# SHIELD.net
KiCad netlist of a schematic drawn in EAGLE
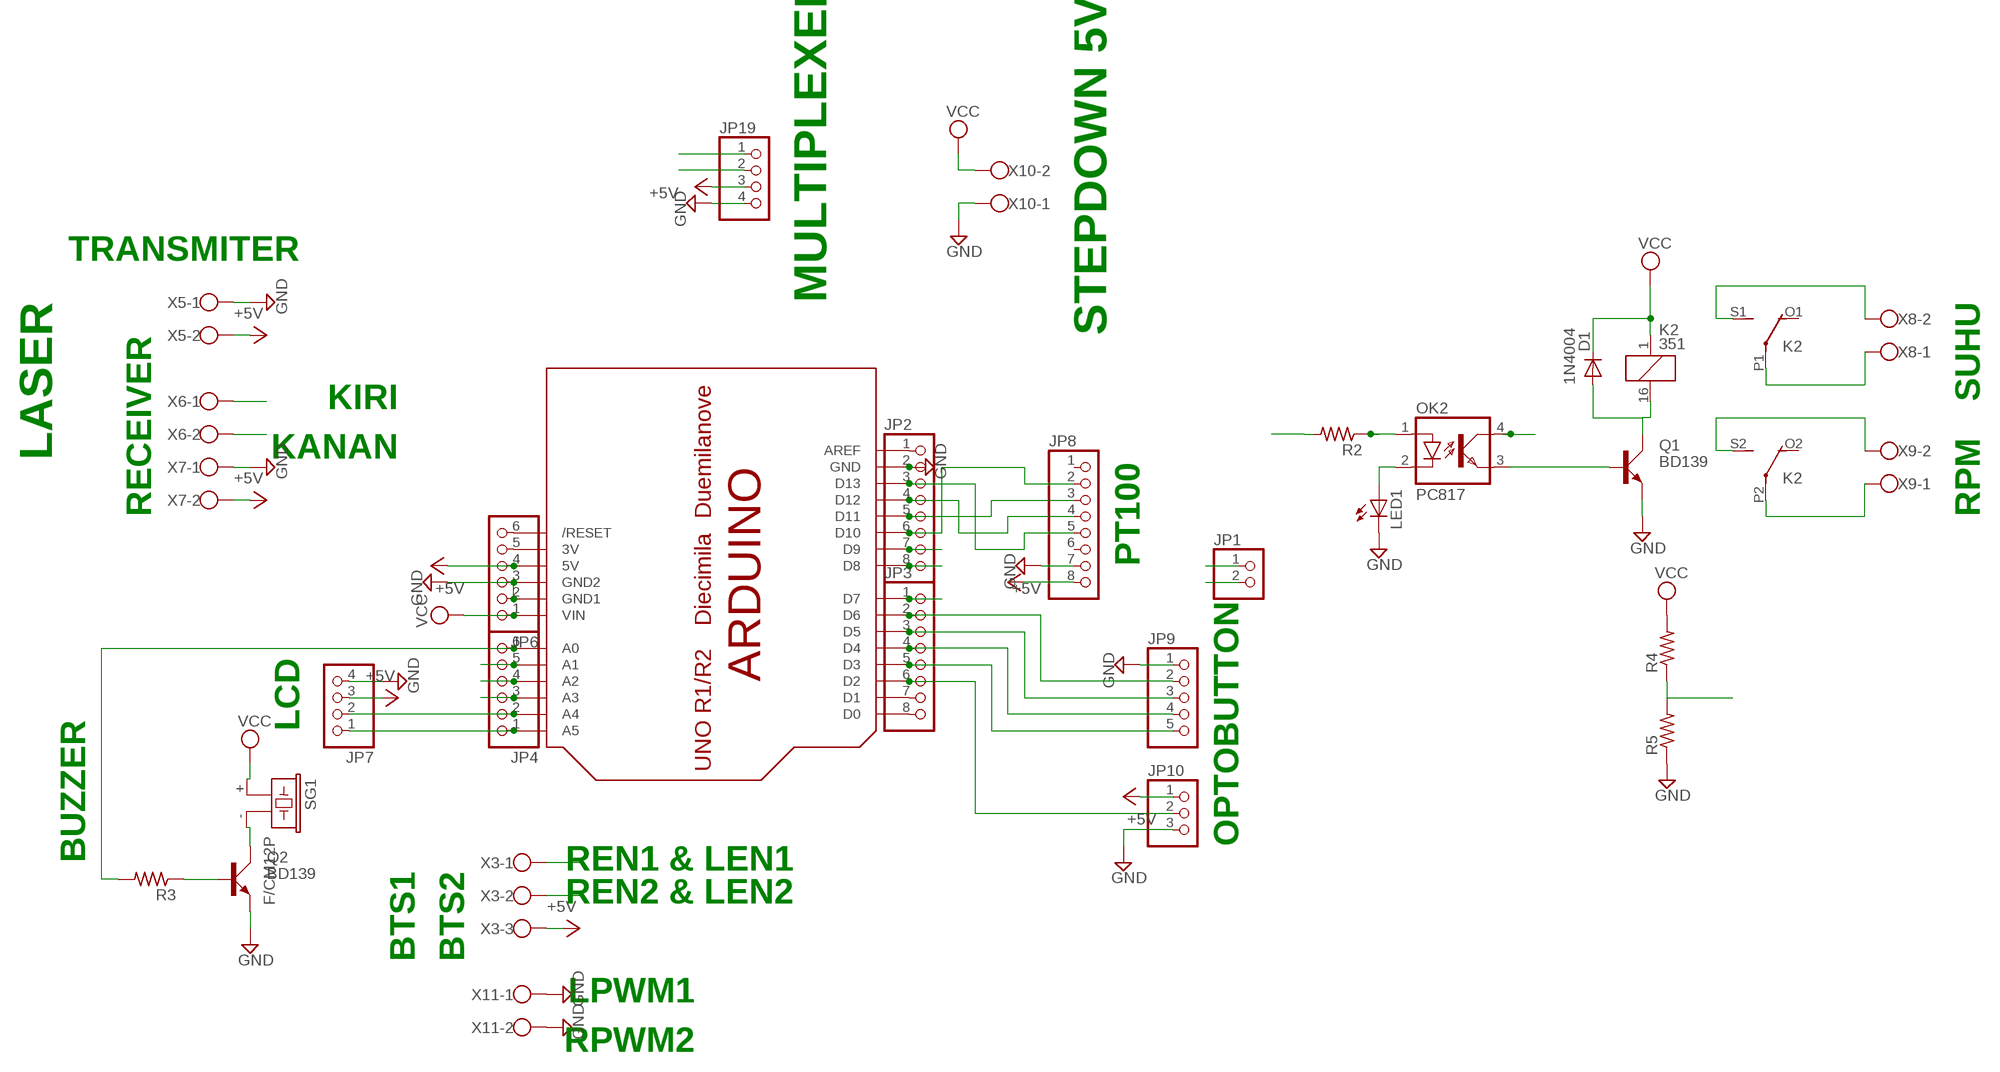
[diagram p0: schematic, sheet 1]

(export (version "E")
  (design (tool "Eeschema 10.0.6"))
  (components
    (comp (ref "D1")
      (value "1N4004")
      (footprint "eagle-import:DO41-10")
      (libsource (lib "eagle-import") (part "1N4004"))
    )
    (comp (ref "JP1")
      (value "PINHD-1X2")
      (footprint "eagle-import:1X02")
      (libsource (lib "eagle-import") (part "PINHD-1X2"))
    )
    (comp (ref "JP2")
      (value "PINHD-1X8")
      (footprint "eagle-import:1X08")
      (libsource (lib "eagle-import") (part "PINHD-1X8"))
    )
    (comp (ref "JP3")
      (value "PINHD-1X8")
      (footprint "eagle-import:1X08")
      (libsource (lib "eagle-import") (part "PINHD-1X8"))
    )
    (comp (ref "JP4")
      (value "PINHD-1X6")
      (footprint "eagle-import:1X06")
      (libsource (lib "eagle-import") (part "PINHD-1X6"))
    )
    (comp (ref "JP6")
      (value "PINHD-1X6")
      (footprint "eagle-import:1X06")
      (libsource (lib "eagle-import") (part "PINHD-1X6"))
    )
    (comp (ref "JP7")
      (value "PINHD-1X4")
      (footprint "eagle-import:1X04")
      (libsource (lib "eagle-import") (part "PINHD-1X4"))
    )
    (comp (ref "JP8")
      (value "PINHD-1X8")
      (footprint "eagle-import:1X08")
      (libsource (lib "eagle-import") (part "PINHD-1X8"))
    )
    (comp (ref "JP9")
      (value "PINHD-1X5")
      (footprint "eagle-import:1X05")
      (libsource (lib "eagle-import") (part "PINHD-1X5"))
    )
    (comp (ref "JP10")
      (value "PINHD-1X3")
      (footprint "eagle-import:1X03")
      (libsource (lib "eagle-import") (part "PINHD-1X3"))
    )
    (comp (ref "JP19")
      (value "PINHD-1X4")
      (footprint "eagle-import:1X04")
      (libsource (lib "eagle-import") (part "PINHD-1X4"))
    )
    (comp (ref "K2")
      (value "351")
      (footprint "eagle-import:351")
      (libsource (lib "eagle-import") (part "351"))
    )
    (comp (ref "LED1")
      (value "LED5MM")
      (footprint "eagle-import:LED5MM")
      (libsource (lib "eagle-import") (part "LED5MM"))
    )
    (comp (ref "OK2")
      (value "PC817")
      (footprint "eagle-import:DIL04")
      (fields (field (name "MPN") "PC817X4J000F"))
      (libsource (lib "eagle-import") (part "PC817"))
    )
    (comp (ref "Q1")
      (value "BD139")
      (footprint "eagle-import:TO126AV")
      (libsource (lib "eagle-import") (part "BD139"))
    )
    (comp (ref "Q2")
      (value "BD139")
      (footprint "eagle-import:TO126AV")
      (libsource (lib "eagle-import") (part "BD139"))
    )
    (comp (ref "R2")
      (value "R-US_0207/10")
      (footprint "eagle-import:0207_10")
      (libsource (lib "eagle-import") (part "R-US_0207/10"))
    )
    (comp (ref "R3")
      (value "R-US_0207/10")
      (footprint "eagle-import:0207_10")
      (libsource (lib "eagle-import") (part "R-US_0207/10"))
    )
    (comp (ref "R4")
      (value "R-US_0207/10")
      (footprint "eagle-import:0207_10")
      (libsource (lib "eagle-import") (part "R-US_0207/10"))
    )
    (comp (ref "R5")
      (value "R-US_0207/10")
      (footprint "eagle-import:0207_10")
      (libsource (lib "eagle-import") (part "R-US_0207/10"))
    )
    (comp (ref "SG1")
      (value "F/CM12P")
      (footprint "eagle-import:F_CM12P")
      (libsource (lib "eagle-import") (part "F/CM12P"))
    )
    (comp (ref "U$1")
      (value "ARDUINO-NOHOLE")
      (footprint "eagle-import:ARDUINO-NOHOLE")
      (libsource (lib "eagle-import") (part "ARDUINO-NOHOLE"))
    )
    (comp (ref "X3")
      (value "W237-103")
      (footprint "eagle-import:W237-103")
      (fields (field (name "MPN") "237-103"))
      (libsource (lib "eagle-import") (part "W237-103"))
    )
    (comp (ref "X5")
      (value "W237-102")
      (footprint "eagle-import:W237-102")
      (fields (field (name "MPN") "237-102"))
      (libsource (lib "eagle-import") (part "W237-102"))
    )
    (comp (ref "X6")
      (value "W237-102")
      (footprint "eagle-import:W237-102")
      (fields (field (name "MPN") "237-102"))
      (libsource (lib "eagle-import") (part "W237-102"))
    )
    (comp (ref "X7")
      (value "W237-102")
      (footprint "eagle-import:W237-102")
      (fields (field (name "MPN") "237-102"))
      (libsource (lib "eagle-import") (part "W237-102"))
    )
    (comp (ref "X8")
      (value "W237-102")
      (footprint "eagle-import:W237-102")
      (fields (field (name "MPN") "237-102"))
      (libsource (lib "eagle-import") (part "W237-102"))
    )
    (comp (ref "X9")
      (value "W237-102")
      (footprint "eagle-import:W237-102")
      (fields (field (name "MPN") "237-102"))
      (libsource (lib "eagle-import") (part "W237-102"))
    )
    (comp (ref "X10")
      (value "W237-102")
      (footprint "eagle-import:W237-102")
      (fields (field (name "MPN") "237-102"))
      (libsource (lib "eagle-import") (part "W237-102"))
    )
    (comp (ref "X11")
      (value "W237-102")
      (footprint "eagle-import:W237-102")
      (fields (field (name "MPN") "237-102"))
      (libsource (lib "eagle-import") (part "W237-102"))
    )
  )
  (nets
    (net (code "1") (name "+5V") (class "Default")
      (node (ref "JP10") (pin "1") (pinfunction "1_1") (pintype "passive"))
      (node (ref "JP19") (pin "3") (pinfunction "3_3") (pintype "passive"))
      (node (ref "JP6") (pin "4") (pinfunction "4_4") (pintype "passive"))
      (node (ref "JP7") (pin "3") (pinfunction "3_3") (pintype "passive"))
      (node (ref "JP8") (pin "8") (pinfunction "8_8") (pintype "passive"))
      (node (ref "U$1") (pin "5V") (pinfunction "5V_5V") (pintype "power_in"))
      (node (ref "X3") (pin "3") (pinfunction "KL_3") (pintype "passive"))
      (node (ref "X5") (pin "2") (pinfunction "KL_2") (pintype "passive"))
      (node (ref "X7") (pin "2") (pinfunction "KL_2") (pintype "passive"))
    )
    (net (code "2") (name "/N$1") (class "Default")
      (node (ref "JP1") (pin "1") (pinfunction "1_1") (pintype "passive"))
      (node (ref "JP1") (pin "2") (pinfunction "2_2") (pintype "passive"))
      (node (ref "JP2") (pin "7") (pinfunction "7_7") (pintype "passive"))
      (node (ref "U$1") (pin "D9") (pinfunction "D9_D9") (pintype "bidirectional"))
    )
    (net (code "3") (name "/N$9") (class "Default")
      (node (ref "JP19") (pin "2") (pinfunction "2_2") (pintype "passive"))
      (node (ref "JP4") (pin "2") (pinfunction "2_2") (pintype "passive"))
      (node (ref "JP7") (pin "2") (pinfunction "2_2") (pintype "passive"))
      (node (ref "U$1") (pin "A4") (pinfunction "A4_A4") (pintype "bidirectional"))
    )
    (net (code "4") (name "/N$10") (class "Default")
      (node (ref "JP19") (pin "1") (pinfunction "1_1") (pintype "passive"))
      (node (ref "JP4") (pin "1") (pinfunction "1_1") (pintype "passive"))
      (node (ref "JP7") (pin "1") (pinfunction "1_1") (pintype "passive"))
      (node (ref "U$1") (pin "A5") (pinfunction "A5_A5") (pintype "bidirectional"))
    )
    (net (code "5") (name "/N$26") (class "Default")
      (node (ref "JP4") (pin "4") (pinfunction "4_4") (pintype "passive"))
      (node (ref "U$1") (pin "A2") (pinfunction "A2_A2") (pintype "bidirectional"))
      (node (ref "X3") (pin "2") (pinfunction "KL_2") (pintype "passive"))
    )
    (net (code "6") (name "/N$27") (class "Default")
      (node (ref "JP3") (pin "1") (pinfunction "1_1") (pintype "passive"))
      (node (ref "U$1") (pin "D7") (pinfunction "D7_D7") (pintype "bidirectional"))
      (node (ref "X6") (pin "2") (pinfunction "KL_2") (pintype "passive"))
    )
    (net (code "7") (name "/N$28") (class "Default")
      (node (ref "JP4") (pin "5") (pinfunction "5_5") (pintype "passive"))
      (node (ref "U$1") (pin "A1") (pinfunction "A1_A1") (pintype "bidirectional"))
      (node (ref "X3") (pin "1") (pinfunction "KL_1") (pintype "passive"))
    )
    (net (code "8") (name "/N$29") (class "Default")
      (node (ref "JP2") (pin "8") (pinfunction "8_8") (pintype "passive"))
      (node (ref "U$1") (pin "D8") (pinfunction "D8_D8") (pintype "bidirectional"))
      (node (ref "X6") (pin "1") (pinfunction "KL_1") (pintype "passive"))
    )
    (net (code "9") (name "/N$32") (class "Default")
      (node (ref "JP4") (pin "3") (pinfunction "3_3") (pintype "passive"))
      (node (ref "R2") (pin "2") (pinfunction "2_2") (pintype "passive"))
      (node (ref "U$1") (pin "A3") (pinfunction "A3_A3") (pintype "bidirectional"))
    )
    (net (code "10") (name "/N$37") (class "Default")
      (node (ref "OK2") (pin "4") (pinfunction "COL_4") (pintype "passive"))
      (node (ref "R4") (pin "1") (pinfunction "1_1") (pintype "passive"))
      (node (ref "R5") (pin "2") (pinfunction "2_2") (pintype "passive"))
    )
    (net (code "11") (name "GND") (class "Default")
      (node (ref "JP10") (pin "3") (pinfunction "3_3") (pintype "passive"))
      (node (ref "JP19") (pin "4") (pinfunction "4_4") (pintype "passive"))
      (node (ref "JP2") (pin "2") (pinfunction "2_2") (pintype "passive"))
      (node (ref "JP6") (pin "2") (pinfunction "2_2") (pintype "passive"))
      (node (ref "JP6") (pin "3") (pinfunction "3_3") (pintype "passive"))
      (node (ref "JP7") (pin "4") (pinfunction "4_4") (pintype "passive"))
      (node (ref "JP8") (pin "7") (pinfunction "7_7") (pintype "passive"))
      (node (ref "JP9") (pin "1") (pinfunction "1_1") (pintype "passive"))
      (node (ref "LED1") (pin "K") (pinfunction "C_K") (pintype "passive"))
      (node (ref "Q1") (pin "E") (pinfunction "E_E") (pintype "passive"))
      (node (ref "Q2") (pin "E") (pinfunction "E_E") (pintype "passive"))
      (node (ref "R5") (pin "1") (pinfunction "1_1") (pintype "passive"))
      (node (ref "U$1") (pin "GND") (pinfunction "GND_GND") (pintype "power_in"))
      (node (ref "U$1") (pin "GND1") (pinfunction "GND1_GND1") (pintype "power_in"))
      (node (ref "U$1") (pin "GND2") (pinfunction "GND2_GND2") (pintype "power_in"))
      (node (ref "X10") (pin "1") (pinfunction "KL_1") (pintype "passive"))
      (node (ref "X11") (pin "1") (pinfunction "KL_1") (pintype "passive"))
      (node (ref "X11") (pin "2") (pinfunction "KL_2") (pintype "passive"))
      (node (ref "X5") (pin "1") (pinfunction "KL_1") (pintype "passive"))
      (node (ref "X7") (pin "1") (pinfunction "KL_1") (pintype "passive"))
    )
    (net (code "12") (name "Net-(JP2-Pad1)") (class "Default")
      (node (ref "JP2") (pin "1") (pinfunction "1_1") (pintype "passive"))
      (node (ref "U$1") (pin "AREF") (pinfunction "AREF_AREF") (pintype "bidirectional"))
    )
    (net (code "13") (name "Net-(JP2-Pad3)") (class "Default")
      (node (ref "JP2") (pin "3") (pinfunction "3_3") (pintype "passive"))
      (node (ref "JP8") (pin "5") (pinfunction "5_5") (pintype "passive"))
      (node (ref "U$1") (pin "D13") (pinfunction "D13_D13") (pintype "bidirectional"))
    )
    (net (code "14") (name "Net-(JP2-Pad4)") (class "Default")
      (node (ref "JP2") (pin "4") (pinfunction "4_4") (pintype "passive"))
      (node (ref "JP8") (pin "4") (pinfunction "4_4") (pintype "passive"))
      (node (ref "U$1") (pin "D12") (pinfunction "D12_D12") (pintype "bidirectional"))
    )
    (net (code "15") (name "Net-(JP2-Pad5)") (class "Default")
      (node (ref "JP2") (pin "5") (pinfunction "5_5") (pintype "passive"))
      (node (ref "JP8") (pin "3") (pinfunction "3_3") (pintype "passive"))
      (node (ref "U$1") (pin "D11") (pinfunction "D11_D11") (pintype "bidirectional"))
    )
    (net (code "16") (name "Net-(JP2-Pad6)") (class "Default")
      (node (ref "JP2") (pin "6") (pinfunction "6_6") (pintype "passive"))
      (node (ref "JP8") (pin "2") (pinfunction "2_2") (pintype "passive"))
      (node (ref "U$1") (pin "D10") (pinfunction "D10_D10") (pintype "bidirectional"))
    )
    (net (code "17") (name "Net-(JP3-Pad2)") (class "Default")
      (node (ref "JP3") (pin "2") (pinfunction "2_2") (pintype "passive"))
      (node (ref "JP9") (pin "2") (pinfunction "2_2") (pintype "passive"))
      (node (ref "U$1") (pin "D6") (pinfunction "D6_D6") (pintype "bidirectional"))
    )
    (net (code "18") (name "Net-(JP3-Pad3)") (class "Default")
      (node (ref "JP3") (pin "3") (pinfunction "3_3") (pintype "passive"))
      (node (ref "JP9") (pin "3") (pinfunction "3_3") (pintype "passive"))
      (node (ref "U$1") (pin "D5") (pinfunction "D5_D5") (pintype "bidirectional"))
    )
    (net (code "19") (name "Net-(JP3-Pad4)") (class "Default")
      (node (ref "JP3") (pin "4") (pinfunction "4_4") (pintype "passive"))
      (node (ref "JP9") (pin "4") (pinfunction "4_4") (pintype "passive"))
      (node (ref "U$1") (pin "D4") (pinfunction "D4_D4") (pintype "bidirectional"))
    )
    (net (code "20") (name "Net-(JP3-Pad5)") (class "Default")
      (node (ref "JP3") (pin "5") (pinfunction "5_5") (pintype "passive"))
      (node (ref "JP9") (pin "5") (pinfunction "5_5") (pintype "passive"))
      (node (ref "U$1") (pin "D3") (pinfunction "D3_D3") (pintype "bidirectional"))
    )
    (net (code "21") (name "Net-(JP3-Pad7)") (class "Default")
      (node (ref "JP3") (pin "7") (pinfunction "7_7") (pintype "passive"))
      (node (ref "U$1") (pin "D1") (pinfunction "D1_D1") (pintype "bidirectional"))
    )
    (net (code "22") (name "Net-(JP3-Pad8)") (class "Default")
      (node (ref "JP3") (pin "8") (pinfunction "8_8") (pintype "passive"))
      (node (ref "U$1") (pin "D0") (pinfunction "D0_D0") (pintype "bidirectional"))
    )
    (net (code "23") (name "Net-(JP4-Pad6)") (class "Default")
      (node (ref "JP4") (pin "6") (pinfunction "6_6") (pintype "passive"))
      (node (ref "R3") (pin "2") (pinfunction "2_2") (pintype "passive"))
      (node (ref "U$1") (pin "A0") (pinfunction "A0_A0") (pintype "bidirectional"))
    )
    (net (code "24") (name "Net-(JP6-Pad5)") (class "Default")
      (node (ref "JP6") (pin "5") (pinfunction "5_5") (pintype "passive"))
      (node (ref "U$1") (pin "3V") (pinfunction "3V_3V") (pintype "power_in"))
    )
    (net (code "25") (name "Net-(JP10-Pad2)") (class "Default")
      (node (ref "JP10") (pin "2") (pinfunction "2_2") (pintype "passive"))
      (node (ref "JP3") (pin "6") (pinfunction "6_6") (pintype "passive"))
      (node (ref "U$1") (pin "D2") (pinfunction "D2_D2") (pintype "bidirectional"))
    )
    (net (code "26") (name "Net-(K2A-2)") (class "Default")
      (node (ref "D1") (pin "A") (pinfunction "A_A") (pintype "passive"))
      (node (ref "K2") (pin "16") (pinfunction "2_16") (pintype "passive"))
      (node (ref "Q1") (pin "C") (pinfunction "C_C") (pintype "passive"))
    )
    (net (code "27") (name "Net-(K2B-P)") (class "Default")
      (node (ref "K2") (pin "P1") (pinfunction "P_P1") (pintype "passive"))
      (node (ref "X8") (pin "1") (pinfunction "KL_1") (pintype "passive"))
    )
    (net (code "28") (name "Net-(K2B-S)") (class "Default")
      (node (ref "K2") (pin "S1") (pinfunction "S_S1") (pintype "passive"))
      (node (ref "X8") (pin "2") (pinfunction "KL_2") (pintype "passive"))
    )
    (net (code "29") (name "Net-(K2C-P)") (class "Default")
      (node (ref "K2") (pin "P2") (pinfunction "P_P2") (pintype "passive"))
      (node (ref "X9") (pin "1") (pinfunction "KL_1") (pintype "passive"))
    )
    (net (code "30") (name "Net-(K2C-S)") (class "Default")
      (node (ref "K2") (pin "S2") (pinfunction "S_S2") (pintype "passive"))
      (node (ref "X9") (pin "2") (pinfunction "KL_2") (pintype "passive"))
    )
    (net (code "31") (name "Net-(OK2-A)") (class "Default")
      (node (ref "OK2") (pin "1") (pinfunction "A_1") (pintype "passive"))
      (node (ref "R2") (pin "1") (pinfunction "1_1") (pintype "passive"))
    )
    (net (code "32") (name "Net-(OK2-C)") (class "Default")
      (node (ref "LED1") (pin "A") (pinfunction "A_A") (pintype "passive"))
      (node (ref "OK2") (pin "2") (pinfunction "C_2") (pintype "passive"))
    )
    (net (code "33") (name "Net-(OK2-EMIT)") (class "Default")
      (node (ref "OK2") (pin "3") (pinfunction "EMIT_3") (pintype "passive"))
      (node (ref "Q1") (pin "B") (pinfunction "B_B") (pintype "passive"))
    )
    (net (code "34") (name "Net-(Q2-PadB)") (class "Default")
      (node (ref "Q2") (pin "B") (pinfunction "B_B") (pintype "passive"))
      (node (ref "R3") (pin "1") (pinfunction "1_1") (pintype "passive"))
    )
    (net (code "35") (name "Net-(SG1-2)") (class "Default")
      (node (ref "Q2") (pin "C") (pinfunction "C_C") (pintype "passive"))
      (node (ref "SG1") (pin "-") (pinfunction "2_-") (pintype "passive"))
    )
    (net (code "36") (name "Net-(U$1-{slash}RESET)") (class "Default")
      (node (ref "JP6") (pin "6") (pinfunction "6_6") (pintype "passive"))
      (node (ref "U$1") (pin "RESET") (pinfunction "/RESET_RESET") (pintype "bidirectional"))
    )
    (net (code "37") (name "VCC") (class "Default")
      (node (ref "D1") (pin "C") (pinfunction "C_C") (pintype "passive"))
      (node (ref "JP6") (pin "1") (pinfunction "1_1") (pintype "passive"))
      (node (ref "K2") (pin "1") (pinfunction "1_1") (pintype "passive"))
      (node (ref "R4") (pin "2") (pinfunction "2_2") (pintype "passive"))
      (node (ref "SG1") (pin "+") (pinfunction "1_+") (pintype "passive"))
      (node (ref "U$1") (pin "VIN") (pinfunction "VIN_VIN") (pintype "power_in"))
      (node (ref "X10") (pin "2") (pinfunction "KL_2") (pintype "passive"))
    )
    (net (code "38") (name "unconnected-(JP8-Pad1)") (class "Default")
      (node (ref "JP8") (pin "1") (pinfunction "1_1") (pintype "passive"))
    )
    (net (code "39") (name "unconnected-(JP8-Pad6)") (class "Default")
      (node (ref "JP8") (pin "6") (pinfunction "6_6") (pintype "passive"))
    )
    (net (code "40") (name "unconnected-(K2B-O-PadO1)") (class "Default")
      (node (ref "K2") (pin "O1") (pinfunction "O_O1") (pintype "passive"))
    )
    (net (code "41") (name "unconnected-(K2C-O-PadO2)") (class "Default")
      (node (ref "K2") (pin "O2") (pinfunction "O_O2") (pintype "passive"))
    )
  )
)
